# 05_-_CPU_-_PCIE_SATA.net
KiCad netlist of a schematic drawn in Altium Designer
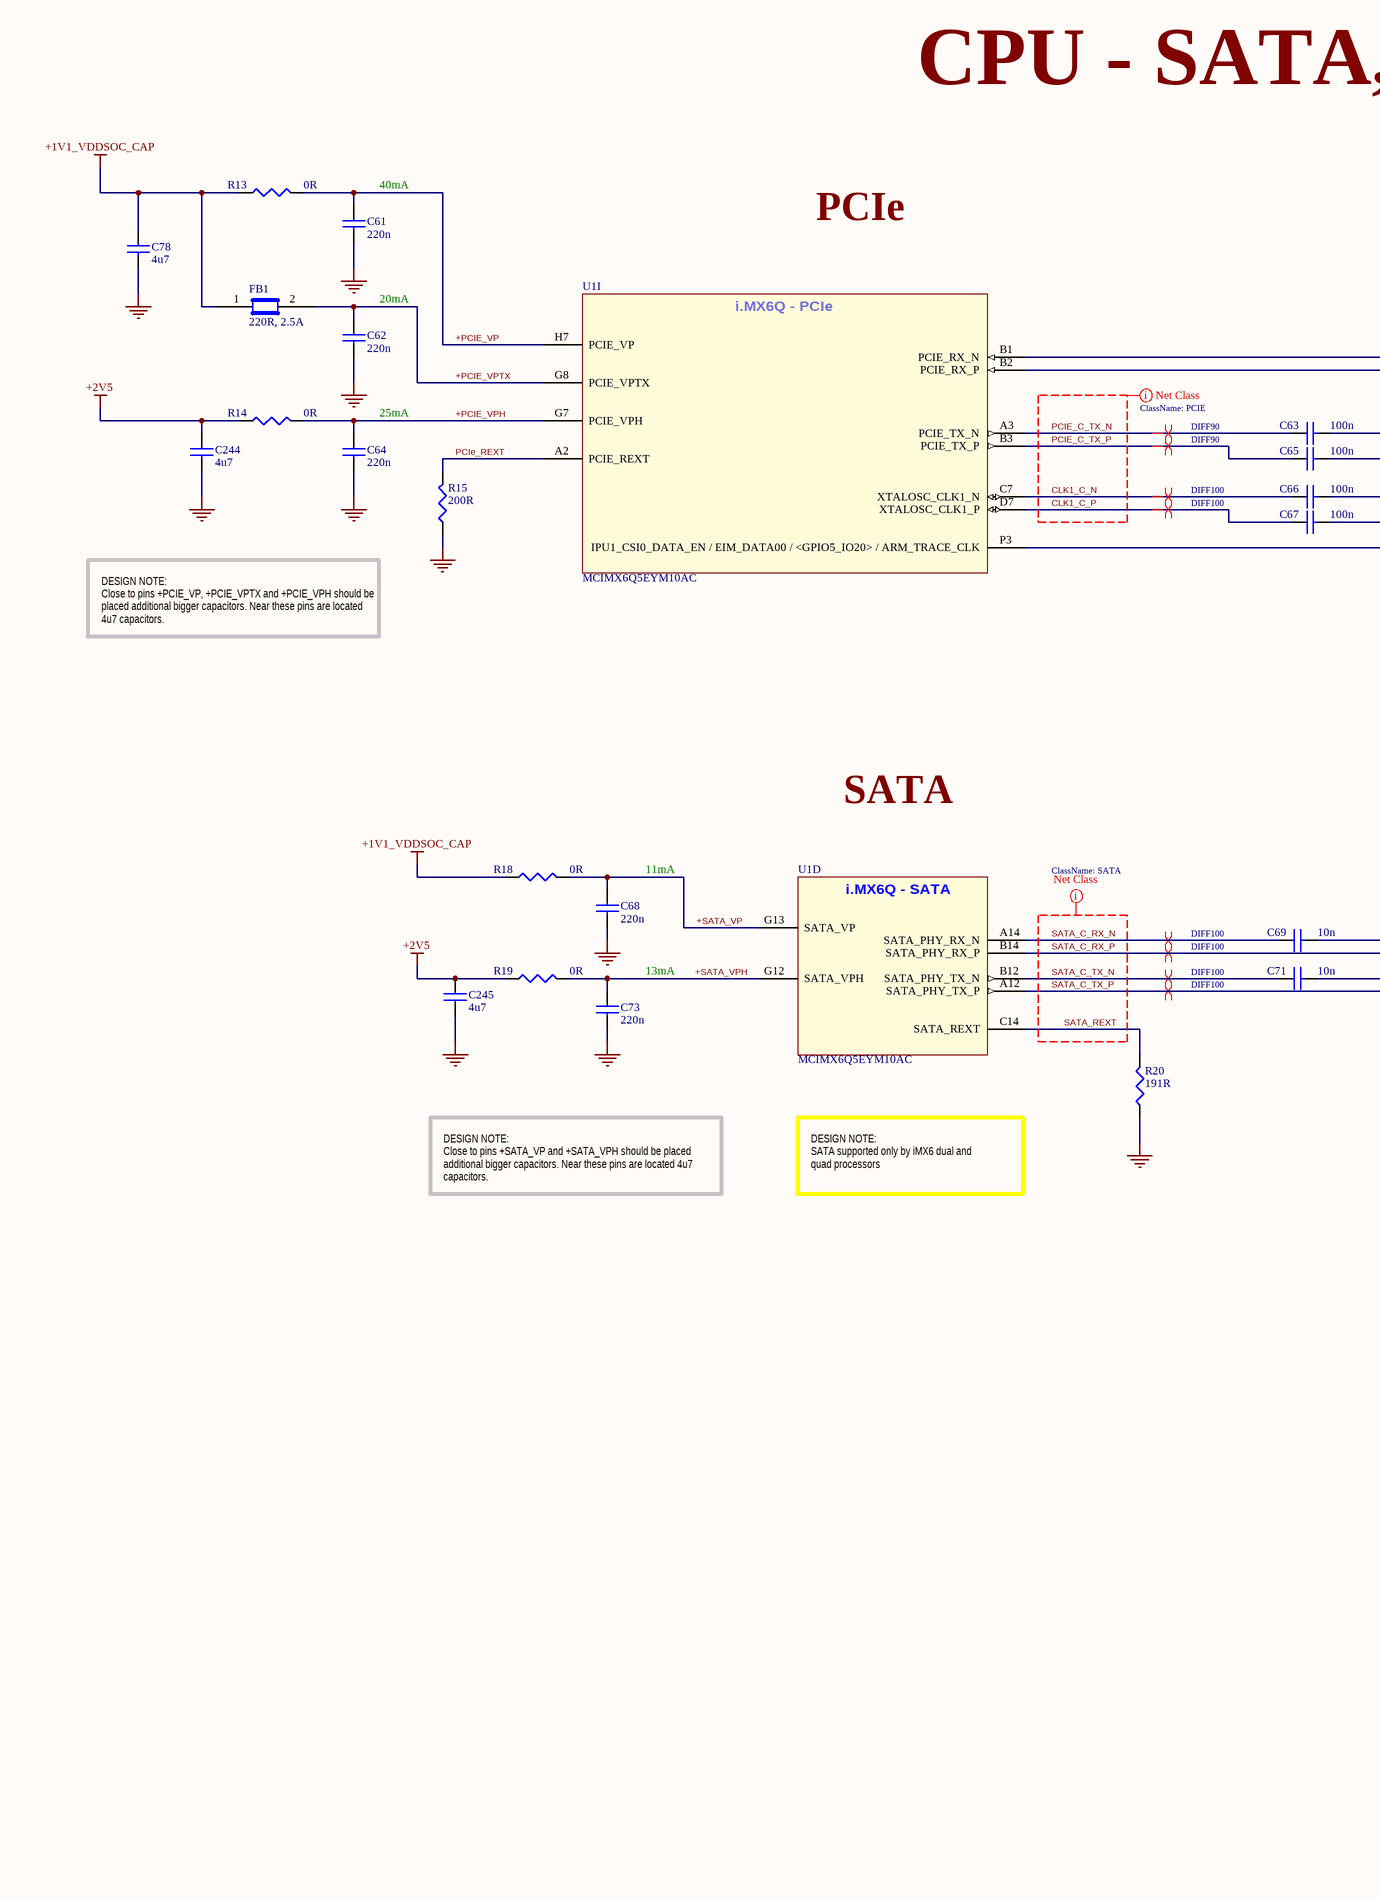
[diagram p0: [05] - CPU - PCIE, SATA.SchDoc, left]
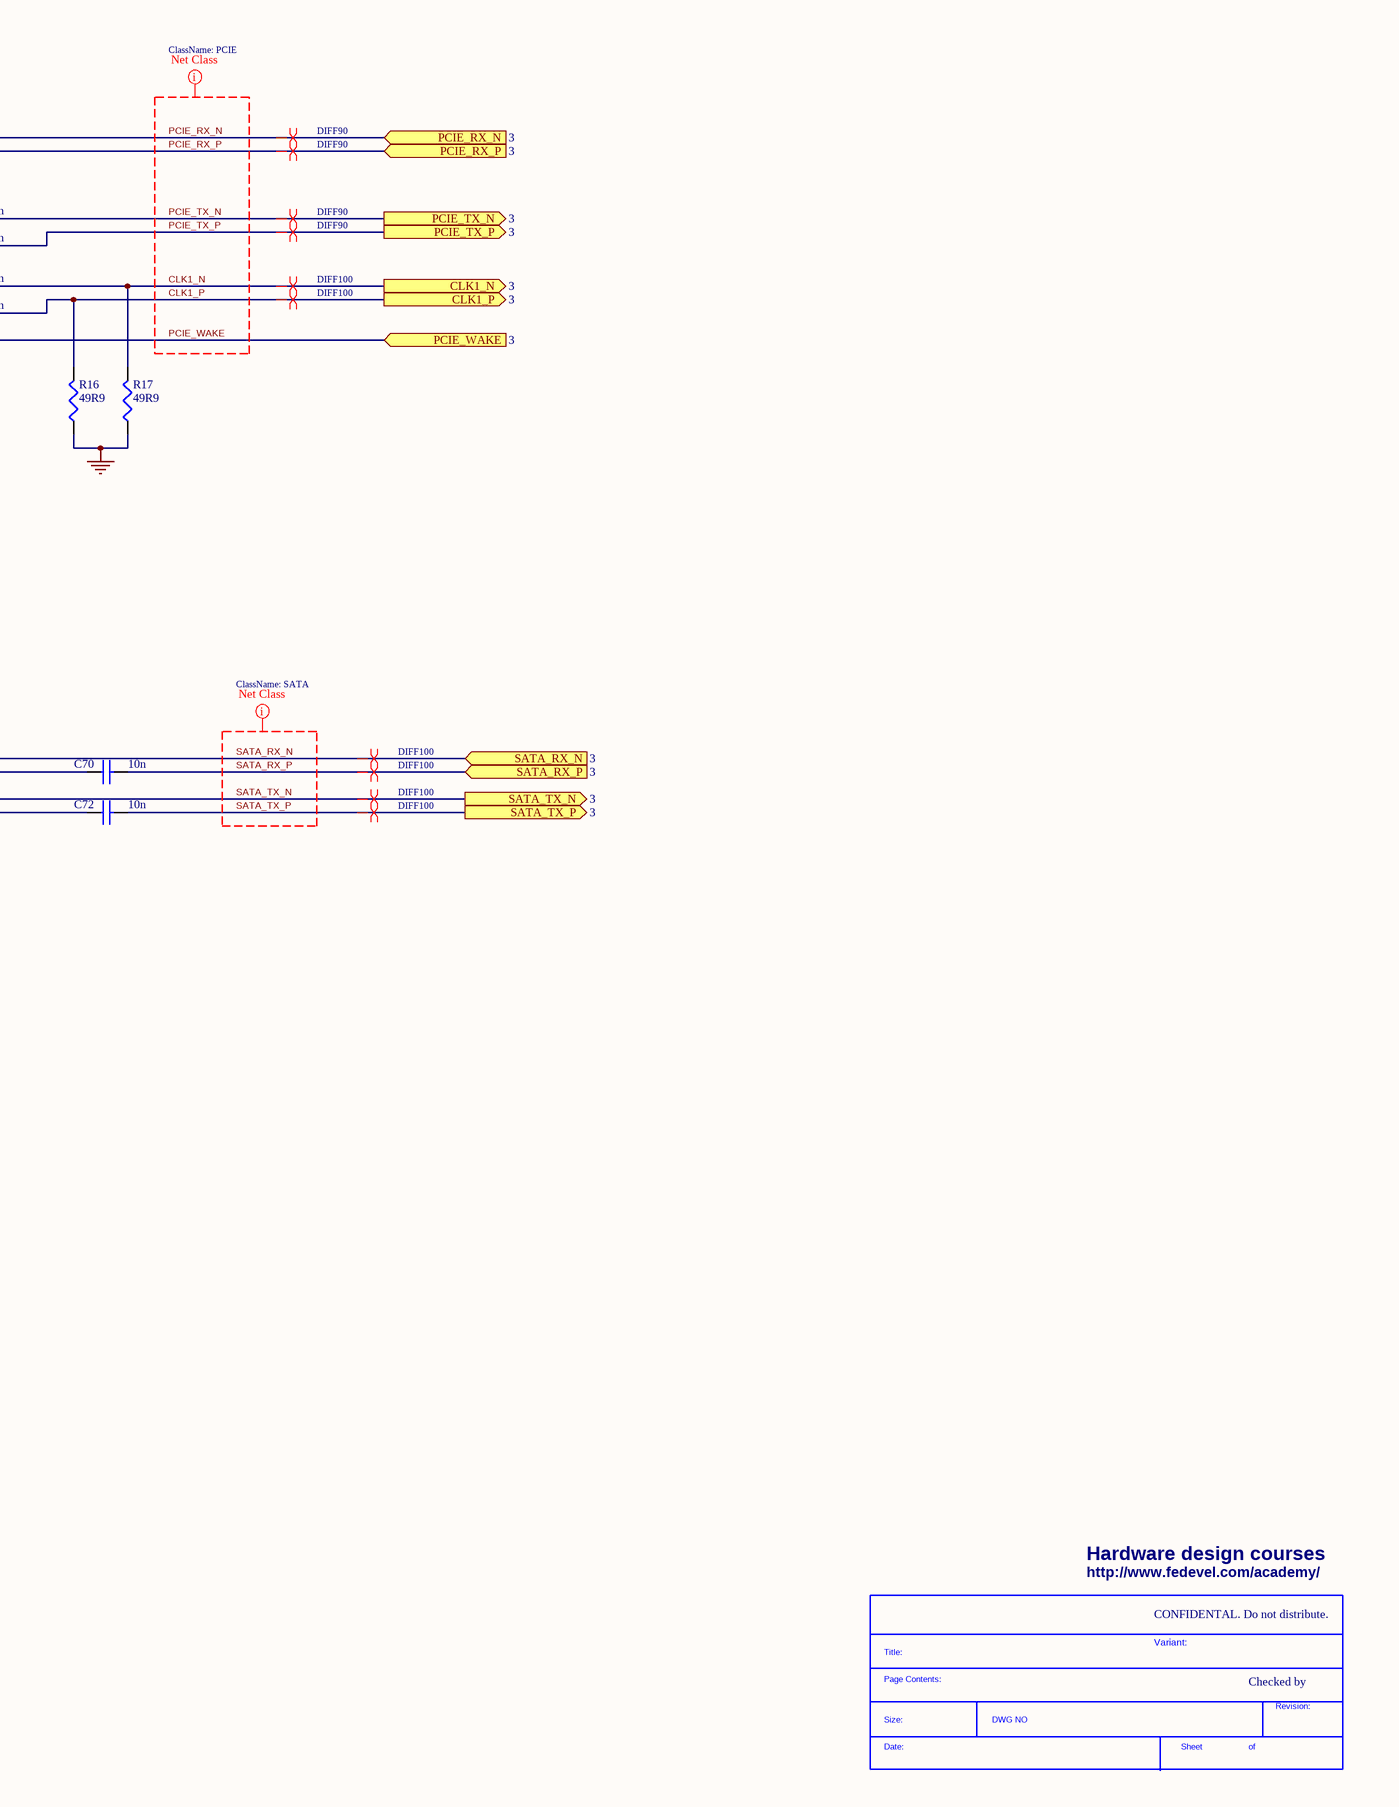
[diagram p1: [05] - CPU - PCIE, SATA.SchDoc, right]

(export (version "E")
  (design (tool "Eeschema 10.0.6"))
  (components
    (comp (ref "C61")
      (value "220n")
      (footprint "C0402")
      (description "CAP CER .22UF 25V X5R 20% 0402")
      (fields
        (field (name "MANUFACTURER") "TDK Corporation")
        (field (name "MANUFACTURER PART NUMBER") "C1005X5R1E224M")
      )
      (libsource (lib "Integrated_Library_RF_FEB_2012") (part "C1005X5R1E224M"))
    )
    (comp (ref "C62")
      (value "220n")
      (footprint "C0402")
      (description "CAP CER .22UF 25V X5R 20% 0402")
      (fields
        (field (name "MANUFACTURER") "TDK Corporation")
        (field (name "MANUFACTURER PART NUMBER") "C1005X5R1E224M")
      )
      (libsource (lib "Integrated_Library_RF_FEB_2012") (part "C1005X5R1E224M"))
    )
    (comp (ref "C63")
      (value "100n")
      (footprint "C0402")
      (description "CAP CER .10UF 50V X5R 10% 0402")
      (fields
        (field (name "MANUFACTURER") "TDK Corporation")
        (field (name "MANUFACTURER PART NUMBER") "C1005X5R1H104K")
      )
      (libsource (lib "Integrated_Library_RF_FEB_2012") (part "C1005X5R1H104K"))
    )
    (comp (ref "C64")
      (value "220n")
      (footprint "C0402")
      (description "CAP CER .22UF 25V X5R 20% 0402")
      (fields
        (field (name "MANUFACTURER") "TDK Corporation")
        (field (name "MANUFACTURER PART NUMBER") "C1005X5R1E224M")
      )
      (libsource (lib "Integrated_Library_RF_FEB_2012") (part "C1005X5R1E224M"))
    )
    (comp (ref "C65")
      (value "100n")
      (footprint "C0402")
      (description "CAP CER .10UF 50V X5R 10% 0402")
      (fields
        (field (name "MANUFACTURER") "TDK Corporation")
        (field (name "MANUFACTURER PART NUMBER") "C1005X5R1H104K")
      )
      (libsource (lib "Integrated_Library_RF_FEB_2012") (part "C1005X5R1H104K"))
    )
    (comp (ref "C66")
      (value "100n")
      (footprint "C0402")
      (description "CAP CER .10UF 50V X5R 10% 0402")
      (fields
        (field (name "MANUFACTURER") "TDK Corporation")
        (field (name "MANUFACTURER PART NUMBER") "C1005X5R1H104K")
      )
      (libsource (lib "Integrated_Library_RF_FEB_2012") (part "C1005X5R1H104K"))
    )
    (comp (ref "C67")
      (value "100n")
      (footprint "C0402")
      (description "CAP CER .10UF 50V X5R 10% 0402")
      (fields
        (field (name "MANUFACTURER") "TDK Corporation")
        (field (name "MANUFACTURER PART NUMBER") "C1005X5R1H104K")
      )
      (libsource (lib "Integrated_Library_RF_FEB_2012") (part "C1005X5R1H104K"))
    )
    (comp (ref "C68")
      (value "220n")
      (footprint "C0402")
      (description "CAP CER .22UF 25V X5R 20% 0402")
      (fields
        (field (name "MANUFACTURER") "TDK Corporation")
        (field (name "MANUFACTURER PART NUMBER") "C1005X5R1E224M")
      )
      (libsource (lib "Integrated_Library_RF_FEB_2012") (part "C1005X5R1E224M"))
    )
    (comp (ref "C69")
      (value "10n")
      (footprint "C0402")
      (description "CAP CER 10000PF 50V 10% X7R 0402")
      (fields
        (field (name "MANUFACTURER") "TDK Corporation")
        (field (name "MANUFACTURER PART NUMBER") "C1005X7R1H103K")
        (field (name ".CHECKED PCB") "RF")
        (field (name ".CHECKED SCH") "RF")
      )
      (libsource (lib "Integrated_Library_RF_FEB_2012") (part "C1005X7R1H103K"))
    )
    (comp (ref "C70")
      (value "10n")
      (footprint "C0402")
      (description "CAP CER 10000PF 50V 10% X7R 0402")
      (fields
        (field (name "MANUFACTURER") "TDK Corporation")
        (field (name "MANUFACTURER PART NUMBER") "C1005X7R1H103K")
        (field (name ".CHECKED PCB") "RF")
        (field (name ".CHECKED SCH") "RF")
      )
      (libsource (lib "Integrated_Library_RF_FEB_2012") (part "C1005X7R1H103K"))
    )
    (comp (ref "C71")
      (value "10n")
      (footprint "C0402")
      (description "CAP CER 10000PF 50V 10% X7R 0402")
      (fields
        (field (name "MANUFACTURER") "TDK Corporation")
        (field (name "MANUFACTURER PART NUMBER") "C1005X7R1H103K")
        (field (name ".CHECKED PCB") "RF")
        (field (name ".CHECKED SCH") "RF")
      )
      (libsource (lib "Integrated_Library_RF_FEB_2012") (part "C1005X7R1H103K"))
    )
    (comp (ref "C72")
      (value "10n")
      (footprint "C0402")
      (description "CAP CER 10000PF 50V 10% X7R 0402")
      (fields
        (field (name "MANUFACTURER") "TDK Corporation")
        (field (name "MANUFACTURER PART NUMBER") "C1005X7R1H103K")
        (field (name ".CHECKED PCB") "RF")
        (field (name ".CHECKED SCH") "RF")
      )
      (libsource (lib "Integrated_Library_RF_FEB_2012") (part "C1005X7R1H103K"))
    )
    (comp (ref "C73")
      (value "220n")
      (footprint "C0402")
      (description "CAP CER .22UF 25V X5R 20% 0402")
      (fields
        (field (name "MANUFACTURER") "TDK Corporation")
        (field (name "MANUFACTURER PART NUMBER") "C1005X5R1E224M")
      )
      (libsource (lib "Integrated_Library_RF_FEB_2012") (part "C1005X5R1E224M"))
    )
    (comp (ref "C78")
      (value "4u7")
      (footprint "C0402")
      (description "CAP CER 4.7UF 10V 20% X5R 0402")
      (fields
        (field (name "MANUFACTURER") "TDK Corporation")
        (field (name "MANUFACTURER PART NUMBER") "C1005X5R1A475M")
        (field (name ".CHECKED PCB") "RF")
        (field (name ".CHECKED SCH") "RF")
      )
      (libsource (lib "Integrated_Library_RF_FEB_2012") (part "C1005X5R1A475M"))
    )
    (comp (ref "C244")
      (value "4u7")
      (footprint "C0402")
      (description "CAP CER 4.7UF 10V 20% X5R 0402")
      (fields
        (field (name "MANUFACTURER") "TDK Corporation")
        (field (name "MANUFACTURER PART NUMBER") "C1005X5R1A475M")
        (field (name ".CHECKED PCB") "RF")
        (field (name ".CHECKED SCH") "RF")
      )
      (libsource (lib "Integrated_Library_RF_FEB_2012") (part "C1005X5R1A475M"))
    )
    (comp (ref "C245")
      (value "4u7")
      (footprint "C0402")
      (description "CAP CER 4.7UF 10V 20% X5R 0402")
      (fields
        (field (name "MANUFACTURER") "TDK Corporation")
        (field (name "MANUFACTURER PART NUMBER") "C1005X5R1A475M")
        (field (name ".CHECKED PCB") "RF")
        (field (name ".CHECKED SCH") "RF")
      )
      (libsource (lib "Integrated_Library_RF_FEB_2012") (part "C1005X5R1A475M"))
    )
    (comp (ref "FB1")
      (value "220R, 2.5A")
      (footprint "C0603")
      (description "FERRITE CHIP 220 OHM 2500MA 0603")
      (fields
        (field (name "MANUFACTURER") "Murata Electronics North America")
        (field (name "MANUFACTURER PART NUMBER") "BLM18SG221TN1D")
        (field (name ".CHECKED PCB") "RF")
        (field (name ".CHECKED SCH") "RF")
      )
      (libsource (lib "Integrated_Library_RF_FEB_2012") (part "BLM18SG221TN1D"))
    )
    (comp (ref "R13")
      (value "0R")
      (footprint "R0402")
      (description "RES 0.0 OHM 1/16W 0402 SMD")
      (fields
        (field (name "MANUFACTURER") "Yageo")
        (field (name "MANUFACTURER PART NUMBER") "RC0402JR-070RL")
      )
      (libsource (lib "Integrated_Library_RF_FEB_2012") (part "RC0402JR-070RL"))
    )
    (comp (ref "R14")
      (value "0R")
      (footprint "R0402")
      (description "RES 0.0 OHM 1/16W 0402 SMD")
      (fields
        (field (name "MANUFACTURER") "Yageo")
        (field (name "MANUFACTURER PART NUMBER") "RC0402JR-070RL")
      )
      (libsource (lib "Integrated_Library_RF_FEB_2012") (part "RC0402JR-070RL"))
    )
    (comp (ref "R15")
      (value "200R")
      (footprint "R0402")
      (description "RES 200 OHM 1/16W 1% 0402 SMD")
      (fields
        (field (name "MANUFACTURER") "Vishay Dale")
        (field (name "MANUFACTURER PART NUMBER") "CRCW0402200RFKED")
        (field (name ".CHECKED PCB") "RF, used by MM")
        (field (name ".CHECKED SCH") "MM, checked by RF")
        (field (name ".CREATOR") "MM")
      )
      (libsource (lib "Schlib_RF") (part "CRCW0402200RFKED"))
    )
    (comp (ref "R16")
      (value "49R9")
      (footprint "R0402")
      (description "RES 49.9 OHM 1/16W 1% 0402 SMD")
      (fields
        (field (name "MANUFACTURER") "Yageo")
        (field (name "MANUFACTURER PART NUMBER") "RC0402FR-0749R9L")
      )
      (libsource (lib "Integrated_Library_RF_FEB_2012") (part "RC0402FR-0749R9L"))
    )
    (comp (ref "R17")
      (value "49R9")
      (footprint "R0402")
      (description "RES 49.9 OHM 1/16W 1% 0402 SMD")
      (fields
        (field (name "MANUFACTURER") "Yageo")
        (field (name "MANUFACTURER PART NUMBER") "RC0402FR-0749R9L")
      )
      (libsource (lib "Integrated_Library_RF_FEB_2012") (part "RC0402FR-0749R9L"))
    )
    (comp (ref "R18")
      (value "0R")
      (footprint "R0402")
      (description "RES 0.0 OHM 1/16W 0402 SMD")
      (fields
        (field (name "MANUFACTURER") "Yageo")
        (field (name "MANUFACTURER PART NUMBER") "RC0402JR-070RL")
      )
      (libsource (lib "Integrated_Library_RF_FEB_2012") (part "RC0402JR-070RL"))
    )
    (comp (ref "R19")
      (value "0R")
      (footprint "R0402")
      (description "RES 0.0 OHM 1/16W 0402 SMD")
      (fields
        (field (name "MANUFACTURER") "Yageo")
        (field (name "MANUFACTURER PART NUMBER") "RC0402JR-070RL")
      )
      (libsource (lib "Integrated_Library_RF_FEB_2012") (part "RC0402JR-070RL"))
    )
    (comp (ref "R20")
      (value "191R")
      (footprint "R0402")
      (description "RES 191 OHM 1/16W 1% 0402 SMD")
      (fields
        (field (name "MANUFACTURER") "Vishay Dale")
        (field (name "MANUFACTURER PART NUMBER") "CRCW0402191RFKED")
        (field (name ".CREATOR") "MM")
        (field (name ".CHECKED PCB") "RF, used by MM")
        (field (name ".CHECKED SCH") "MM, checked by RF")
      )
      (libsource (lib "Schlib_RF") (part "CRCW0402191RFKED"))
    )
    (comp (ref "U1")
      (value "MCIMX6Q5EYM10AC")
      (footprint "PBGA624")
      (description "IC MCU 32BIT ARM QUAD 624FCBGA")
      (fields
        (field (name "MANUFACTURER") "Freescale Semiconductor")
        (field (name ".CREATOR") "MM")
        (field (name ".CHECKED PCB") "MM, checked by RF")
        (field (name ".CHECKED SCH") "MM")
      )
      (libsource (lib "Schlib_RF") (part "MCIMX6Q5EYM10AC"))
    )
  )
  (nets
    (net (code "1") (name "+1V1_VDDSOC_CAP") (class "Default")
      (node (ref "C78") (pin "1") (pinfunction "1_1") (pintype "passive"))
      (node (ref "FB1") (pin "1") (pinfunction "1_1") (pintype "passive"))
      (node (ref "R13") (pin "1") (pinfunction "1_1") (pintype "passive"))
      (node (ref "R18") (pin "1") (pinfunction "1_1") (pintype "passive"))
    )
    (net (code "2") (name "+2V5") (class "Default")
      (node (ref "C244") (pin "1") (pinfunction "1_1") (pintype "passive"))
      (node (ref "C245") (pin "1") (pinfunction "1_1") (pintype "passive"))
      (node (ref "R14") (pin "1") (pinfunction "1_1") (pintype "passive"))
      (node (ref "R19") (pin "1") (pinfunction "1_1") (pintype "passive"))
    )
    (net (code "3") (name "/+PCIE_VP") (class "Default")
      (node (ref "C61") (pin "1") (pinfunction "1_1") (pintype "passive"))
      (node (ref "R13") (pin "2") (pinfunction "2_2") (pintype "passive"))
      (node (ref "U1") (pin "H7") (pinfunction "PCIE_VP_H7") (pintype "power_in"))
    )
    (net (code "4") (name "/+PCIE_VPH") (class "Default")
      (node (ref "C64") (pin "1") (pinfunction "1_1") (pintype "passive"))
      (node (ref "R14") (pin "2") (pinfunction "2_2") (pintype "passive"))
      (node (ref "U1") (pin "G7") (pinfunction "PCIE_VPH_G7") (pintype "power_in"))
    )
    (net (code "5") (name "/+PCIE_VPTX") (class "Default")
      (node (ref "C62") (pin "1") (pinfunction "1_1") (pintype "passive"))
      (node (ref "FB1") (pin "2") (pinfunction "2_2") (pintype "passive"))
      (node (ref "U1") (pin "G8") (pinfunction "PCIE_VPTX_G8") (pintype "power_in"))
    )
    (net (code "6") (name "/+SATA_VP") (class "Default")
      (node (ref "C68") (pin "1") (pinfunction "1_1") (pintype "passive"))
      (node (ref "R18") (pin "2") (pinfunction "2_2") (pintype "passive"))
      (node (ref "U1") (pin "G13") (pinfunction "SATA_VP_G13") (pintype "power_in"))
    )
    (net (code "7") (name "/+SATA_VPH") (class "Default")
      (node (ref "C73") (pin "1") (pinfunction "1_1") (pintype "passive"))
      (node (ref "R19") (pin "2") (pinfunction "2_2") (pintype "passive"))
      (node (ref "U1") (pin "G12") (pinfunction "SATA_VPH_G12") (pintype "power_in"))
    )
    (net (code "8") (name "/CLK1_C_N") (class "Default")
      (node (ref "C66") (pin "1") (pinfunction "1_1") (pintype "passive"))
      (node (ref "U1") (pin "C7") (pinfunction "XTALOSC_CLK1_N_C7") (pintype "bidirectional"))
    )
    (net (code "9") (name "/CLK1_C_P") (class "Default")
      (node (ref "C67") (pin "1") (pinfunction "1_1") (pintype "passive"))
      (node (ref "U1") (pin "D7") (pinfunction "XTALOSC_CLK1_P_D7") (pintype "bidirectional"))
    )
    (net (code "10") (name "/CLK1_N") (class "Default")
      (node (ref "C66") (pin "2") (pinfunction "2_2") (pintype "passive"))
      (node (ref "R17") (pin "2") (pinfunction "2_2") (pintype "passive"))
    )
    (net (code "11") (name "/CLK1_P") (class "Default")
      (node (ref "C67") (pin "2") (pinfunction "2_2") (pintype "passive"))
      (node (ref "R16") (pin "2") (pinfunction "2_2") (pintype "passive"))
    )
    (net (code "12") (name "/PCIE_C_TX_N") (class "Default")
      (node (ref "C63") (pin "1") (pinfunction "1_1") (pintype "passive"))
      (node (ref "U1") (pin "A3") (pinfunction "PCIE_TX_N_A3") (pintype "output"))
    )
    (net (code "13") (name "/PCIE_C_TX_P") (class "Default")
      (node (ref "C65") (pin "1") (pinfunction "1_1") (pintype "passive"))
      (node (ref "U1") (pin "B3") (pinfunction "PCIE_TX_P_B3") (pintype "output"))
    )
    (net (code "14") (name "/PCIE_RX_N") (class "Default")
      (node (ref "U1") (pin "B1") (pinfunction "PCIE_RX_N_B1") (pintype "input"))
    )
    (net (code "15") (name "/PCIE_RX_P") (class "Default")
      (node (ref "U1") (pin "B2") (pinfunction "PCIE_RX_P_B2") (pintype "input"))
    )
    (net (code "16") (name "/PCIE_TX_N") (class "Default")
      (node (ref "C63") (pin "2") (pinfunction "2_2") (pintype "passive"))
    )
    (net (code "17") (name "/PCIE_TX_P") (class "Default")
      (node (ref "C65") (pin "2") (pinfunction "2_2") (pintype "passive"))
    )
    (net (code "18") (name "/PCIE_WAKE") (class "Default")
      (node (ref "U1") (pin "P3") (pinfunction "IPU1_CSI0_DATA_EN_/_EIM_DATA00_/_<GPIO5_IO20>_/_ARM_TRACE_CLK_P3") (pintype "passive"))
    )
    (net (code "19") (name "/PCIe_REXT") (class "Default")
      (node (ref "R15") (pin "2") (pinfunction "2_2") (pintype "passive"))
      (node (ref "U1") (pin "A2") (pinfunction "PCIE_REXT_A2") (pintype "passive"))
    )
    (net (code "20") (name "/SATA_C_RX_N") (class "Default")
      (node (ref "C69") (pin "1") (pinfunction "1_1") (pintype "passive"))
      (node (ref "U1") (pin "A14") (pinfunction "SATA_PHY_RX_N_A14") (pintype "passive"))
    )
    (net (code "21") (name "/SATA_C_RX_P") (class "Default")
      (node (ref "C70") (pin "1") (pinfunction "1_1") (pintype "passive"))
      (node (ref "U1") (pin "B14") (pinfunction "SATA_PHY_RX_P_B14") (pintype "passive"))
    )
    (net (code "22") (name "/SATA_C_TX_N") (class "Default")
      (node (ref "C71") (pin "1") (pinfunction "1_1") (pintype "passive"))
      (node (ref "U1") (pin "B12") (pinfunction "SATA_PHY_TX_N_B12") (pintype "output"))
    )
    (net (code "23") (name "/SATA_C_TX_P") (class "Default")
      (node (ref "C72") (pin "1") (pinfunction "1_1") (pintype "passive"))
      (node (ref "U1") (pin "A12") (pinfunction "SATA_PHY_TX_P_A12") (pintype "output"))
    )
    (net (code "24") (name "/SATA_REXT") (class "Default")
      (node (ref "R20") (pin "2") (pinfunction "2_2") (pintype "passive"))
      (node (ref "U1") (pin "C14") (pinfunction "SATA_REXT_C14") (pintype "passive"))
    )
    (net (code "25") (name "/SATA_RX_N") (class "Default")
      (node (ref "C69") (pin "2") (pinfunction "2_2") (pintype "passive"))
    )
    (net (code "26") (name "/SATA_RX_P") (class "Default")
      (node (ref "C70") (pin "2") (pinfunction "2_2") (pintype "passive"))
    )
    (net (code "27") (name "/SATA_TX_N") (class "Default")
      (node (ref "C71") (pin "2") (pinfunction "2_2") (pintype "passive"))
    )
    (net (code "28") (name "/SATA_TX_P") (class "Default")
      (node (ref "C72") (pin "2") (pinfunction "2_2") (pintype "passive"))
    )
    (net (code "29") (name "GND") (class "Default")
      (node (ref "C244") (pin "2") (pinfunction "2_2") (pintype "passive"))
      (node (ref "C245") (pin "2") (pinfunction "2_2") (pintype "passive"))
      (node (ref "C61") (pin "2") (pinfunction "2_2") (pintype "passive"))
      (node (ref "C62") (pin "2") (pinfunction "2_2") (pintype "passive"))
      (node (ref "C64") (pin "2") (pinfunction "2_2") (pintype "passive"))
      (node (ref "C68") (pin "2") (pinfunction "2_2") (pintype "passive"))
      (node (ref "C73") (pin "2") (pinfunction "2_2") (pintype "passive"))
      (node (ref "C78") (pin "2") (pinfunction "2_2") (pintype "passive"))
      (node (ref "R15") (pin "1") (pinfunction "1_1") (pintype "passive"))
      (node (ref "R16") (pin "1") (pinfunction "1_1") (pintype "passive"))
      (node (ref "R17") (pin "1") (pinfunction "1_1") (pintype "passive"))
      (node (ref "R20") (pin "1") (pinfunction "1_1") (pintype "passive"))
    )
  )
)
